# encoder_board.net
KiCad netlist of a schematic drawn in EAGLE
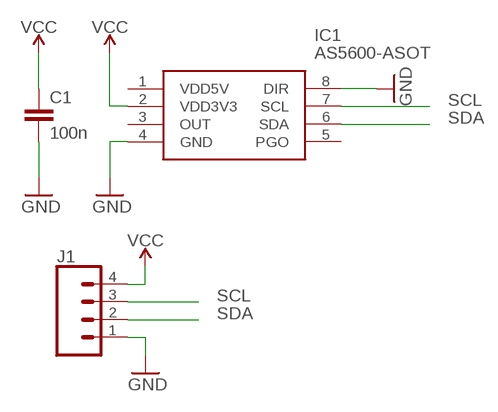
[diagram p0: schematic, sheet 1]

(export (version "E")
  (design (tool "Eeschema 10.0.6"))
  (components
    (comp (ref "C1")
      (value "100n")
      (footprint "eagle-import:C0805")
      (libsource (lib "eagle-import") (part "C-EUC0805"))
    )
    (comp (ref "IC1")
      (value "AS5600-ASOT")
      (footprint "eagle-import:SOIC127P600X175-8N")
      (fields (field (name "MOUSER_PART_NUMBER") "985-AS5600-ASOT"))
      (libsource (lib "eagle-import") (part "AS5600-ASOT"))
    )
    (comp (ref "J1")
      (value "CONN_04LONGPADS")
      (footprint "eagle-import:1X04_LONGPADS")
      (libsource (lib "eagle-import") (part "CONN_04LONGPADS"))
    )
  )
  (nets
    (net (code "1") (name "/SCL") (class "Default")
      (node (ref "IC1") (pin "7") (pinfunction "SCL_7") (pintype "bidirectional"))
      (node (ref "J1") (pin "3") (pinfunction "3_3") (pintype "passive"))
    )
    (net (code "2") (name "/SDA") (class "Default")
      (node (ref "IC1") (pin "6") (pinfunction "SDA_6") (pintype "bidirectional"))
      (node (ref "J1") (pin "2") (pinfunction "2_2") (pintype "passive"))
    )
    (net (code "3") (name "GND") (class "Default")
      (node (ref "C1") (pin "2") (pinfunction "2_2") (pintype "passive"))
      (node (ref "IC1") (pin "4") (pinfunction "GND_4") (pintype "bidirectional"))
      (node (ref "IC1") (pin "8") (pinfunction "DIR_8") (pintype "bidirectional"))
      (node (ref "J1") (pin "1") (pinfunction "1_1") (pintype "passive"))
    )
    (net (code "4") (name "VCC") (class "Default")
      (node (ref "C1") (pin "1") (pinfunction "1_1") (pintype "passive"))
      (node (ref "IC1") (pin "2") (pinfunction "VDD3V3_2") (pintype "bidirectional"))
      (node (ref "J1") (pin "4") (pinfunction "4_4") (pintype "passive"))
    )
    (net (code "5") (name "unconnected-(IC1-OUT-Pad3)") (class "Default")
      (node (ref "IC1") (pin "3") (pinfunction "OUT_3") (pintype "bidirectional"))
    )
    (net (code "6") (name "unconnected-(IC1-PGO-Pad5)") (class "Default")
      (node (ref "IC1") (pin "5") (pinfunction "PGO_5") (pintype "bidirectional"))
    )
    (net (code "7") (name "unconnected-(IC1-VDD5V-Pad1)") (class "Default")
      (node (ref "IC1") (pin "1") (pinfunction "VDD5V_1") (pintype "bidirectional"))
    )
  )
)
